# E_Arduino_MEGA2560_ref.net
KiCad netlist of a schematic drawn in EAGLE
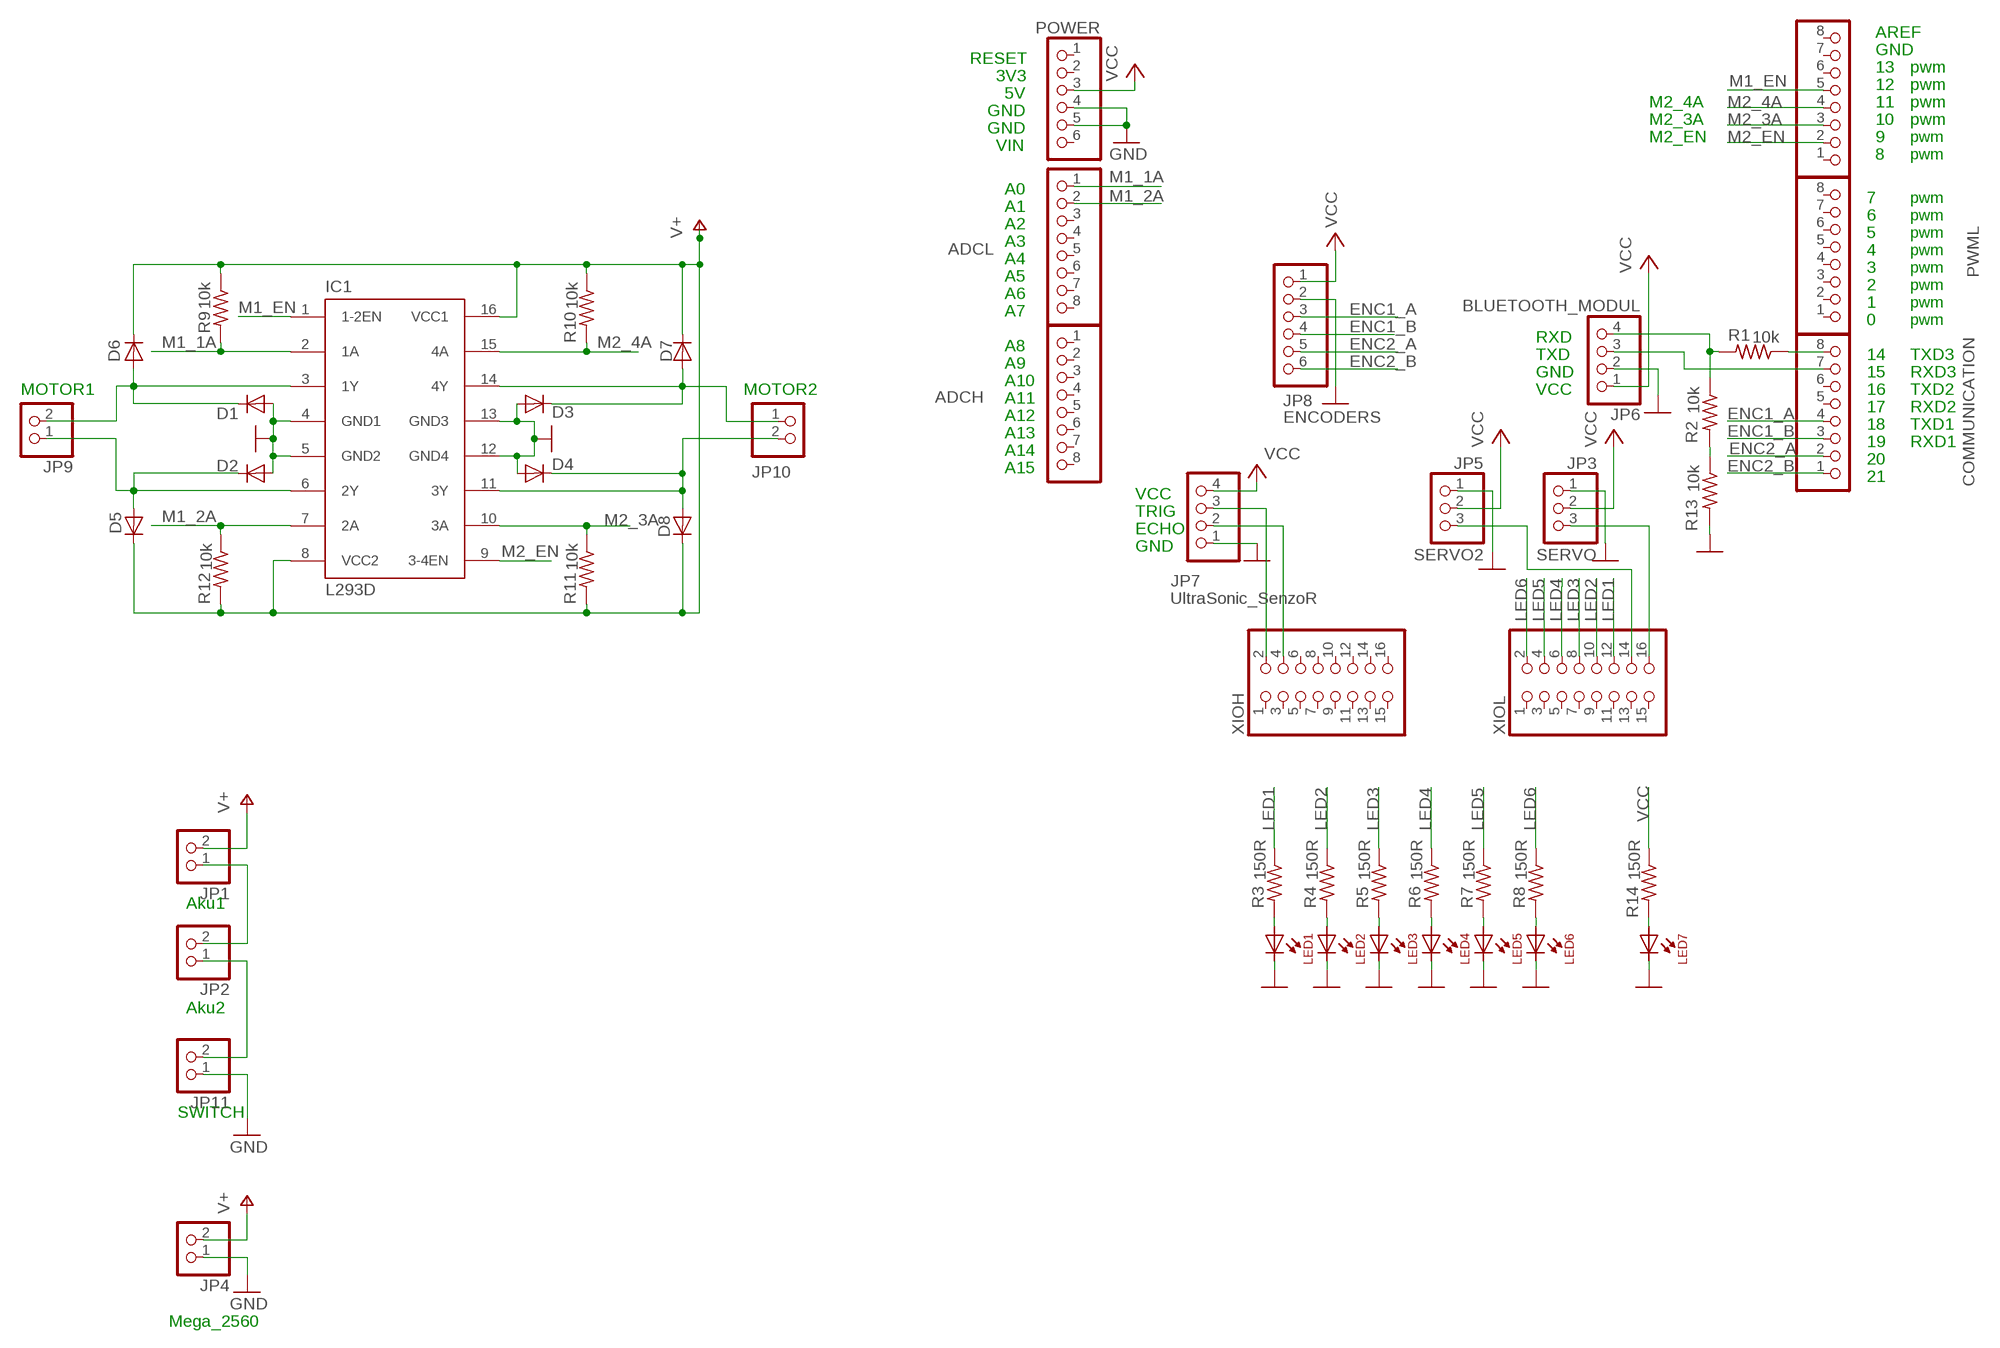
[diagram p0: schematic, sheet 1]

(export (version "E")
  (design (tool "Eeschema 10.0.6"))
  (components
    (comp (ref "ADCH")
      (value "PINHD-1X8")
      (footprint "eagle-import:1X08")
      (libsource (lib "eagle-import") (part "PINHD-1X8"))
    )
    (comp (ref "ADCL")
      (value "PINHD-1X8")
      (footprint "eagle-import:1X08")
      (libsource (lib "eagle-import") (part "PINHD-1X8"))
    )
    (comp (ref "COMMUNICATION")
      (value "PINHD-1X8")
      (footprint "eagle-import:1X08")
      (libsource (lib "eagle-import") (part "PINHD-1X8"))
    )
    (comp (ref "D1")
      (value "PMLL4150")
      (footprint "eagle-import:SOD80C")
      (libsource (lib "eagle-import") (part "PMLL4150"))
    )
    (comp (ref "D2")
      (value "PMLL4150")
      (footprint "eagle-import:SOD80C")
      (libsource (lib "eagle-import") (part "PMLL4150"))
    )
    (comp (ref "D3")
      (value "PMLL4150")
      (footprint "eagle-import:SOD80C")
      (libsource (lib "eagle-import") (part "PMLL4150"))
    )
    (comp (ref "D4")
      (value "PMLL4150")
      (footprint "eagle-import:SOD80C")
      (libsource (lib "eagle-import") (part "PMLL4150"))
    )
    (comp (ref "D5")
      (value "PMLL4150")
      (footprint "eagle-import:SOD80C")
      (libsource (lib "eagle-import") (part "PMLL4150"))
    )
    (comp (ref "D6")
      (value "PMLL4150")
      (footprint "eagle-import:SOD80C")
      (libsource (lib "eagle-import") (part "PMLL4150"))
    )
    (comp (ref "D7")
      (value "PMLL4150")
      (footprint "eagle-import:SOD80C")
      (libsource (lib "eagle-import") (part "PMLL4150"))
    )
    (comp (ref "D8")
      (value "PMLL4150")
      (footprint "eagle-import:SOD80C")
      (libsource (lib "eagle-import") (part "PMLL4150"))
    )
    (comp (ref "IC1")
      (value "L293D")
      (footprint "eagle-import:DIL16")
      (libsource (lib "eagle-import") (part "L293D"))
    )
    (comp (ref "JP1")
      (value "PINHD-1X2")
      (footprint "eagle-import:1X02")
      (libsource (lib "eagle-import") (part "PINHD-1X2"))
    )
    (comp (ref "JP2")
      (value "PINHD-1X2")
      (footprint "eagle-import:1X02")
      (libsource (lib "eagle-import") (part "PINHD-1X2"))
    )
    (comp (ref "JP3")
      (value "SERVO")
      (footprint "eagle-import:1X03")
      (libsource (lib "eagle-import") (part "PINHD-1X3"))
    )
    (comp (ref "JP4")
      (value "PINHD-1X2")
      (footprint "eagle-import:1X02")
      (libsource (lib "eagle-import") (part "PINHD-1X2"))
    )
    (comp (ref "JP5")
      (value "SERVO2")
      (footprint "eagle-import:1X03")
      (libsource (lib "eagle-import") (part "PINHD-1X3"))
    )
    (comp (ref "JP6")
      (value "BLUETOOTH_MODUL")
      (footprint "eagle-import:1X04")
      (libsource (lib "eagle-import") (part "PINHD-1X4"))
    )
    (comp (ref "JP7")
      (value "UltraSonic_SenzoR")
      (footprint "eagle-import:1X04")
      (libsource (lib "eagle-import") (part "PINHD-1X4"))
    )
    (comp (ref "JP8")
      (value "ENCODERS")
      (footprint "eagle-import:1X06")
      (libsource (lib "eagle-import") (part "PINHD-1X6"))
    )
    (comp (ref "JP9")
      (value "PINHD-1X2")
      (footprint "eagle-import:1X02")
      (libsource (lib "eagle-import") (part "PINHD-1X2"))
    )
    (comp (ref "JP10")
      (value "PINHD-1X2")
      (footprint "eagle-import:1X02")
      (libsource (lib "eagle-import") (part "PINHD-1X2"))
    )
    (comp (ref "JP11")
      (value "PINHD-1X2")
      (footprint "eagle-import:1X02")
      (libsource (lib "eagle-import") (part "PINHD-1X2"))
    )
    (comp (ref "LED1")
      (value "LED_Y_SMD")
      (footprint "eagle-import:LED_Y_SMD")
      (libsource (lib "eagle-import") (part "LED_Y_SMD"))
    )
    (comp (ref "LED2")
      (value "LED_Y_SMD")
      (footprint "eagle-import:LED_Y_SMD")
      (libsource (lib "eagle-import") (part "LED_Y_SMD"))
    )
    (comp (ref "LED3")
      (value "LED_Y_SMD")
      (footprint "eagle-import:LED_Y_SMD")
      (libsource (lib "eagle-import") (part "LED_Y_SMD"))
    )
    (comp (ref "LED4")
      (value "LED_Y_SMD")
      (footprint "eagle-import:LED_Y_SMD")
      (libsource (lib "eagle-import") (part "LED_Y_SMD"))
    )
    (comp (ref "LED5")
      (value "LED_Y_SMD")
      (footprint "eagle-import:LED_Y_SMD")
      (libsource (lib "eagle-import") (part "LED_Y_SMD"))
    )
    (comp (ref "LED6")
      (value "LED_Y_SMD")
      (footprint "eagle-import:LED_Y_SMD")
      (libsource (lib "eagle-import") (part "LED_Y_SMD"))
    )
    (comp (ref "LED7")
      (value "LED_Y_SMD")
      (footprint "eagle-import:LED_Y_SMD")
      (libsource (lib "eagle-import") (part "LED_Y_SMD"))
    )
    (comp (ref "POWER")
      (value "PINHD-1X6")
      (footprint "eagle-import:1X06")
      (libsource (lib "eagle-import") (part "PINHD-1X6"))
    )
    (comp (ref "PWMH")
      (value "PINHD-1X8")
      (footprint "eagle-import:1X08")
      (libsource (lib "eagle-import") (part "PINHD-1X8"))
    )
    (comp (ref "PWML")
      (value "PINHD-1X8")
      (footprint "eagle-import:1X08")
      (libsource (lib "eagle-import") (part "PINHD-1X8"))
    )
    (comp (ref "R1")
      (value "10k")
      (footprint "eagle-import:R0805")
      (libsource (lib "eagle-import") (part "R-US_R0805"))
    )
    (comp (ref "R2")
      (value "10k")
      (footprint "eagle-import:R0805")
      (libsource (lib "eagle-import") (part "R-US_R0805"))
    )
    (comp (ref "R3")
      (value "150R")
      (footprint "eagle-import:R0805")
      (libsource (lib "eagle-import") (part "R-US_R0805"))
    )
    (comp (ref "R4")
      (value "150R")
      (footprint "eagle-import:R0805")
      (libsource (lib "eagle-import") (part "R-US_R0805"))
    )
    (comp (ref "R5")
      (value "150R")
      (footprint "eagle-import:R0805")
      (libsource (lib "eagle-import") (part "R-US_R0805"))
    )
    (comp (ref "R6")
      (value "150R")
      (footprint "eagle-import:R0805")
      (libsource (lib "eagle-import") (part "R-US_R0805"))
    )
    (comp (ref "R7")
      (value "150R")
      (footprint "eagle-import:R0805")
      (libsource (lib "eagle-import") (part "R-US_R0805"))
    )
    (comp (ref "R8")
      (value "150R")
      (footprint "eagle-import:R0805")
      (libsource (lib "eagle-import") (part "R-US_R0805"))
    )
    (comp (ref "R9")
      (value "10k")
      (footprint "eagle-import:R0805")
      (libsource (lib "eagle-import") (part "R-US_R0805"))
    )
    (comp (ref "R10")
      (value "10k")
      (footprint "eagle-import:R0805")
      (libsource (lib "eagle-import") (part "R-US_R0805"))
    )
    (comp (ref "R11")
      (value "10k")
      (footprint "eagle-import:R0805")
      (libsource (lib "eagle-import") (part "R-US_R0805"))
    )
    (comp (ref "R12")
      (value "10k")
      (footprint "eagle-import:R0805")
      (libsource (lib "eagle-import") (part "R-US_R0805"))
    )
    (comp (ref "R13")
      (value "10k")
      (footprint "eagle-import:R0805")
      (libsource (lib "eagle-import") (part "R-US_R0805"))
    )
    (comp (ref "R14")
      (value "150R")
      (footprint "eagle-import:R0805")
      (libsource (lib "eagle-import") (part "R-US_R0805"))
    )
    (comp (ref "XIOH")
      (value "PINHD-2X8")
      (footprint "eagle-import:2X08")
      (libsource (lib "eagle-import") (part "PINHD-2X8"))
    )
    (comp (ref "XIOL")
      (value "PINHD-2X8")
      (footprint "eagle-import:2X08")
      (libsource (lib "eagle-import") (part "PINHD-2X8"))
    )
  )
  (nets
    (net (code "1") (name "/ENC1_A") (class "Default")
      (node (ref "COMMUNICATION") (pin "4") (pinfunction "4_4") (pintype "passive"))
      (node (ref "JP8") (pin "3") (pinfunction "3_3") (pintype "passive"))
    )
    (net (code "2") (name "/ENC1_B") (class "Default")
      (node (ref "COMMUNICATION") (pin "3") (pinfunction "3_3") (pintype "passive"))
      (node (ref "JP8") (pin "4") (pinfunction "4_4") (pintype "passive"))
    )
    (net (code "3") (name "/ENC2_A") (class "Default")
      (node (ref "COMMUNICATION") (pin "2") (pinfunction "2_2") (pintype "passive"))
      (node (ref "JP8") (pin "5") (pinfunction "5_5") (pintype "passive"))
    )
    (net (code "4") (name "/ENC2_B") (class "Default")
      (node (ref "COMMUNICATION") (pin "1") (pinfunction "1_1") (pintype "passive"))
      (node (ref "JP8") (pin "6") (pinfunction "6_6") (pintype "passive"))
    )
    (net (code "5") (name "/LED1") (class "Default")
      (node (ref "R3") (pin "1") (pinfunction "1_1") (pintype "passive"))
      (node (ref "XIOL") (pin "12") (pinfunction "12_12") (pintype "passive"))
    )
    (net (code "6") (name "/LED2") (class "Default")
      (node (ref "R4") (pin "1") (pinfunction "1_1") (pintype "passive"))
      (node (ref "XIOL") (pin "10") (pinfunction "10_10") (pintype "passive"))
    )
    (net (code "7") (name "/LED3") (class "Default")
      (node (ref "R5") (pin "1") (pinfunction "1_1") (pintype "passive"))
      (node (ref "XIOL") (pin "8") (pinfunction "8_8") (pintype "passive"))
    )
    (net (code "8") (name "/LED4") (class "Default")
      (node (ref "R6") (pin "1") (pinfunction "1_1") (pintype "passive"))
      (node (ref "XIOL") (pin "6") (pinfunction "6_6") (pintype "passive"))
    )
    (net (code "9") (name "/LED5") (class "Default")
      (node (ref "R7") (pin "1") (pinfunction "1_1") (pintype "passive"))
      (node (ref "XIOL") (pin "4") (pinfunction "4_4") (pintype "passive"))
    )
    (net (code "10") (name "/LED6") (class "Default")
      (node (ref "R8") (pin "1") (pinfunction "1_1") (pintype "passive"))
      (node (ref "XIOL") (pin "2") (pinfunction "2_2") (pintype "passive"))
    )
    (net (code "11") (name "/M1_1A") (class "Default")
      (node (ref "ADCL") (pin "1") (pinfunction "1_1") (pintype "passive"))
      (node (ref "IC1") (pin "2") (pinfunction "1A_2") (pintype "input"))
      (node (ref "R9") (pin "2") (pinfunction "2_2") (pintype "passive"))
    )
    (net (code "12") (name "/M1_2A") (class "Default")
      (node (ref "ADCL") (pin "2") (pinfunction "2_2") (pintype "passive"))
      (node (ref "IC1") (pin "7") (pinfunction "2A_7") (pintype "input"))
      (node (ref "R12") (pin "1") (pinfunction "1_1") (pintype "passive"))
    )
    (net (code "13") (name "/M1_EN") (class "Default")
      (node (ref "IC1") (pin "1") (pinfunction "1-2EN_1") (pintype "input"))
      (node (ref "PWMH") (pin "5") (pinfunction "5_5") (pintype "passive"))
    )
    (net (code "14") (name "/M2_3A") (class "Default")
      (node (ref "IC1") (pin "10") (pinfunction "3A_10") (pintype "input"))
      (node (ref "PWMH") (pin "3") (pinfunction "3_3") (pintype "passive"))
      (node (ref "R11") (pin "1") (pinfunction "1_1") (pintype "passive"))
    )
    (net (code "15") (name "/M2_4A") (class "Default")
      (node (ref "IC1") (pin "15") (pinfunction "4A_15") (pintype "input"))
      (node (ref "PWMH") (pin "4") (pinfunction "4_4") (pintype "passive"))
      (node (ref "R10") (pin "2") (pinfunction "2_2") (pintype "passive"))
    )
    (net (code "16") (name "/M2_EN") (class "Default")
      (node (ref "IC1") (pin "9") (pinfunction "3-4EN_9") (pintype "input"))
      (node (ref "PWMH") (pin "2") (pinfunction "2_2") (pintype "passive"))
    )
    (net (code "17") (name "GND") (class "Default")
      (node (ref "D1") (pin "A") (pinfunction "A_A") (pintype "passive"))
      (node (ref "D2") (pin "A") (pinfunction "A_A") (pintype "passive"))
      (node (ref "D3") (pin "A") (pinfunction "A_A") (pintype "passive"))
      (node (ref "D4") (pin "A") (pinfunction "A_A") (pintype "passive"))
      (node (ref "IC1") (pin "12") (pinfunction "GND4_12") (pintype "power_in"))
      (node (ref "IC1") (pin "13") (pinfunction "GND3_13") (pintype "power_in"))
      (node (ref "IC1") (pin "4") (pinfunction "GND1_4") (pintype "power_in"))
      (node (ref "IC1") (pin "5") (pinfunction "GND2_5") (pintype "power_in"))
      (node (ref "JP11") (pin "1") (pinfunction "1_1") (pintype "passive"))
      (node (ref "JP3") (pin "1") (pinfunction "1_1") (pintype "passive"))
      (node (ref "JP4") (pin "1") (pinfunction "1_1") (pintype "passive"))
      (node (ref "JP5") (pin "1") (pinfunction "1_1") (pintype "passive"))
      (node (ref "JP6") (pin "2") (pinfunction "2_2") (pintype "passive"))
      (node (ref "JP7") (pin "1") (pinfunction "1_1") (pintype "passive"))
      (node (ref "JP8") (pin "2") (pinfunction "2_2") (pintype "passive"))
      (node (ref "LED1") (pin "CATHODE") (pinfunction "CATHODE_CATHODE") (pintype "bidirectional"))
      (node (ref "LED2") (pin "CATHODE") (pinfunction "CATHODE_CATHODE") (pintype "bidirectional"))
      (node (ref "LED3") (pin "CATHODE") (pinfunction "CATHODE_CATHODE") (pintype "bidirectional"))
      (node (ref "LED4") (pin "CATHODE") (pinfunction "CATHODE_CATHODE") (pintype "bidirectional"))
      (node (ref "LED5") (pin "CATHODE") (pinfunction "CATHODE_CATHODE") (pintype "bidirectional"))
      (node (ref "LED6") (pin "CATHODE") (pinfunction "CATHODE_CATHODE") (pintype "bidirectional"))
      (node (ref "LED7") (pin "CATHODE") (pinfunction "CATHODE_CATHODE") (pintype "bidirectional"))
      (node (ref "POWER") (pin "4") (pinfunction "4_4") (pintype "passive"))
      (node (ref "POWER") (pin "5") (pinfunction "5_5") (pintype "passive"))
      (node (ref "R13") (pin "2") (pinfunction "2_2") (pintype "passive"))
    )
    (net (code "18") (name "Net-(COMMUNICATION-Pad7)") (class "Default")
      (node (ref "COMMUNICATION") (pin "7") (pinfunction "7_7") (pintype "passive"))
      (node (ref "JP6") (pin "3") (pinfunction "3_3") (pintype "passive"))
    )
    (net (code "19") (name "Net-(COMMUNICATION-Pad8)") (class "Default")
      (node (ref "COMMUNICATION") (pin "8") (pinfunction "8_8") (pintype "passive"))
      (node (ref "R1") (pin "1") (pinfunction "1_1") (pintype "passive"))
    )
    (net (code "20") (name "Net-(IC1-1Y)") (class "Default")
      (node (ref "D1") (pin "C") (pinfunction "C_C") (pintype "passive"))
      (node (ref "D6") (pin "A") (pinfunction "A_A") (pintype "passive"))
      (node (ref "IC1") (pin "3") (pinfunction "1Y_3") (pintype "output"))
      (node (ref "JP9") (pin "2") (pinfunction "2_2") (pintype "passive"))
    )
    (net (code "21") (name "Net-(IC1-2Y)") (class "Default")
      (node (ref "D2") (pin "C") (pinfunction "C_C") (pintype "passive"))
      (node (ref "D5") (pin "A") (pinfunction "A_A") (pintype "passive"))
      (node (ref "IC1") (pin "6") (pinfunction "2Y_6") (pintype "output"))
      (node (ref "JP9") (pin "1") (pinfunction "1_1") (pintype "passive"))
    )
    (net (code "22") (name "Net-(IC1-3Y)") (class "Default")
      (node (ref "D4") (pin "C") (pinfunction "C_C") (pintype "passive"))
      (node (ref "D8") (pin "A") (pinfunction "A_A") (pintype "passive"))
      (node (ref "IC1") (pin "11") (pinfunction "3Y_11") (pintype "output"))
      (node (ref "JP10") (pin "2") (pinfunction "2_2") (pintype "passive"))
    )
    (net (code "23") (name "Net-(IC1-4Y)") (class "Default")
      (node (ref "D3") (pin "C") (pinfunction "C_C") (pintype "passive"))
      (node (ref "D7") (pin "A") (pinfunction "A_A") (pintype "passive"))
      (node (ref "IC1") (pin "14") (pinfunction "4Y_14") (pintype "output"))
      (node (ref "JP10") (pin "1") (pinfunction "1_1") (pintype "passive"))
    )
    (net (code "24") (name "Net-(JP1-Pad1)") (class "Default")
      (node (ref "JP1") (pin "1") (pinfunction "1_1") (pintype "passive"))
      (node (ref "JP2") (pin "2") (pinfunction "2_2") (pintype "passive"))
    )
    (net (code "25") (name "Net-(JP3-Pad3)") (class "Default")
      (node (ref "JP3") (pin "3") (pinfunction "3_3") (pintype "passive"))
      (node (ref "XIOL") (pin "16") (pinfunction "16_16") (pintype "passive"))
    )
    (net (code "26") (name "Net-(JP5-Pad3)") (class "Default")
      (node (ref "JP5") (pin "3") (pinfunction "3_3") (pintype "passive"))
      (node (ref "XIOL") (pin "14") (pinfunction "14_14") (pintype "passive"))
    )
    (net (code "27") (name "Net-(JP6-Pad4)") (class "Default")
      (node (ref "JP6") (pin "4") (pinfunction "4_4") (pintype "passive"))
      (node (ref "R1") (pin "2") (pinfunction "2_2") (pintype "passive"))
      (node (ref "R2") (pin "1") (pinfunction "1_1") (pintype "passive"))
    )
    (net (code "28") (name "Net-(JP7-Pad2)") (class "Default")
      (node (ref "JP7") (pin "2") (pinfunction "2_2") (pintype "passive"))
      (node (ref "XIOH") (pin "4") (pinfunction "4_4") (pintype "passive"))
    )
    (net (code "29") (name "Net-(JP7-Pad3)") (class "Default")
      (node (ref "JP7") (pin "3") (pinfunction "3_3") (pintype "passive"))
      (node (ref "XIOH") (pin "2") (pinfunction "2_2") (pintype "passive"))
    )
    (net (code "30") (name "Net-(JP11-Pad2)") (class "Default")
      (node (ref "JP11") (pin "2") (pinfunction "2_2") (pintype "passive"))
      (node (ref "JP2") (pin "1") (pinfunction "1_1") (pintype "passive"))
    )
    (net (code "31") (name "Net-(LED1-PadANODE)") (class "Default")
      (node (ref "LED1") (pin "ANODE") (pinfunction "ANODE_ANODE") (pintype "bidirectional"))
      (node (ref "R3") (pin "2") (pinfunction "2_2") (pintype "passive"))
    )
    (net (code "32") (name "Net-(LED2-PadANODE)") (class "Default")
      (node (ref "LED2") (pin "ANODE") (pinfunction "ANODE_ANODE") (pintype "bidirectional"))
      (node (ref "R4") (pin "2") (pinfunction "2_2") (pintype "passive"))
    )
    (net (code "33") (name "Net-(LED3-PadANODE)") (class "Default")
      (node (ref "LED3") (pin "ANODE") (pinfunction "ANODE_ANODE") (pintype "bidirectional"))
      (node (ref "R5") (pin "2") (pinfunction "2_2") (pintype "passive"))
    )
    (net (code "34") (name "Net-(LED4-PadANODE)") (class "Default")
      (node (ref "LED4") (pin "ANODE") (pinfunction "ANODE_ANODE") (pintype "bidirectional"))
      (node (ref "R6") (pin "2") (pinfunction "2_2") (pintype "passive"))
    )
    (net (code "35") (name "Net-(LED5-PadANODE)") (class "Default")
      (node (ref "LED5") (pin "ANODE") (pinfunction "ANODE_ANODE") (pintype "bidirectional"))
      (node (ref "R7") (pin "2") (pinfunction "2_2") (pintype "passive"))
    )
    (net (code "36") (name "Net-(LED6-PadANODE)") (class "Default")
      (node (ref "LED6") (pin "ANODE") (pinfunction "ANODE_ANODE") (pintype "bidirectional"))
      (node (ref "R8") (pin "2") (pinfunction "2_2") (pintype "passive"))
    )
    (net (code "37") (name "Net-(LED7-PadANODE)") (class "Default")
      (node (ref "LED7") (pin "ANODE") (pinfunction "ANODE_ANODE") (pintype "bidirectional"))
      (node (ref "R14") (pin "2") (pinfunction "2_2") (pintype "passive"))
    )
    (net (code "38") (name "Net-(R13-Pad1)") (class "Default")
      (node (ref "R13") (pin "1") (pinfunction "1_1") (pintype "passive"))
      (node (ref "R2") (pin "2") (pinfunction "2_2") (pintype "passive"))
    )
    (net (code "39") (name "V+") (class "Default")
      (node (ref "D5") (pin "C") (pinfunction "C_C") (pintype "passive"))
      (node (ref "D6") (pin "C") (pinfunction "C_C") (pintype "passive"))
      (node (ref "D7") (pin "C") (pinfunction "C_C") (pintype "passive"))
      (node (ref "D8") (pin "C") (pinfunction "C_C") (pintype "passive"))
      (node (ref "IC1") (pin "16") (pinfunction "VCC1_16") (pintype "power_in"))
      (node (ref "IC1") (pin "8") (pinfunction "VCC2_8") (pintype "power_in"))
      (node (ref "JP1") (pin "2") (pinfunction "2_2") (pintype "passive"))
      (node (ref "JP4") (pin "2") (pinfunction "2_2") (pintype "passive"))
      (node (ref "R10") (pin "1") (pinfunction "1_1") (pintype "passive"))
      (node (ref "R11") (pin "2") (pinfunction "2_2") (pintype "passive"))
      (node (ref "R12") (pin "2") (pinfunction "2_2") (pintype "passive"))
      (node (ref "R9") (pin "1") (pinfunction "1_1") (pintype "passive"))
    )
    (net (code "40") (name "VCC") (class "Default")
      (node (ref "JP3") (pin "2") (pinfunction "2_2") (pintype "passive"))
      (node (ref "JP5") (pin "2") (pinfunction "2_2") (pintype "passive"))
      (node (ref "JP6") (pin "1") (pinfunction "1_1") (pintype "passive"))
      (node (ref "JP7") (pin "4") (pinfunction "4_4") (pintype "passive"))
      (node (ref "JP8") (pin "1") (pinfunction "1_1") (pintype "passive"))
      (node (ref "POWER") (pin "3") (pinfunction "3_3") (pintype "passive"))
      (node (ref "R14") (pin "1") (pinfunction "1_1") (pintype "passive"))
    )
    (net (code "41") (name "unconnected-(ADCH-Pad1)") (class "Default")
      (node (ref "ADCH") (pin "1") (pinfunction "1_1") (pintype "passive"))
    )
    (net (code "42") (name "unconnected-(ADCH-Pad2)") (class "Default")
      (node (ref "ADCH") (pin "2") (pinfunction "2_2") (pintype "passive"))
    )
    (net (code "43") (name "unconnected-(ADCH-Pad3)") (class "Default")
      (node (ref "ADCH") (pin "3") (pinfunction "3_3") (pintype "passive"))
    )
    (net (code "44") (name "unconnected-(ADCH-Pad4)") (class "Default")
      (node (ref "ADCH") (pin "4") (pinfunction "4_4") (pintype "passive"))
    )
    (net (code "45") (name "unconnected-(ADCH-Pad5)") (class "Default")
      (node (ref "ADCH") (pin "5") (pinfunction "5_5") (pintype "passive"))
    )
    (net (code "46") (name "unconnected-(ADCH-Pad6)") (class "Default")
      (node (ref "ADCH") (pin "6") (pinfunction "6_6") (pintype "passive"))
    )
    (net (code "47") (name "unconnected-(ADCH-Pad7)") (class "Default")
      (node (ref "ADCH") (pin "7") (pinfunction "7_7") (pintype "passive"))
    )
    (net (code "48") (name "unconnected-(ADCH-Pad8)") (class "Default")
      (node (ref "ADCH") (pin "8") (pinfunction "8_8") (pintype "passive"))
    )
    (net (code "49") (name "unconnected-(ADCL-Pad3)") (class "Default")
      (node (ref "ADCL") (pin "3") (pinfunction "3_3") (pintype "passive"))
    )
    (net (code "50") (name "unconnected-(ADCL-Pad4)") (class "Default")
      (node (ref "ADCL") (pin "4") (pinfunction "4_4") (pintype "passive"))
    )
    (net (code "51") (name "unconnected-(ADCL-Pad5)") (class "Default")
      (node (ref "ADCL") (pin "5") (pinfunction "5_5") (pintype "passive"))
    )
    (net (code "52") (name "unconnected-(ADCL-Pad6)") (class "Default")
      (node (ref "ADCL") (pin "6") (pinfunction "6_6") (pintype "passive"))
    )
    (net (code "53") (name "unconnected-(ADCL-Pad7)") (class "Default")
      (node (ref "ADCL") (pin "7") (pinfunction "7_7") (pintype "passive"))
    )
    (net (code "54") (name "unconnected-(ADCL-Pad8)") (class "Default")
      (node (ref "ADCL") (pin "8") (pinfunction "8_8") (pintype "passive"))
    )
    (net (code "55") (name "unconnected-(COMMUNICATION-Pad5)") (class "Default")
      (node (ref "COMMUNICATION") (pin "5") (pinfunction "5_5") (pintype "passive"))
    )
    (net (code "56") (name "unconnected-(COMMUNICATION-Pad6)") (class "Default")
      (node (ref "COMMUNICATION") (pin "6") (pinfunction "6_6") (pintype "passive"))
    )
    (net (code "57") (name "unconnected-(POWER-Pad1)") (class "Default")
      (node (ref "POWER") (pin "1") (pinfunction "1_1") (pintype "passive"))
    )
    (net (code "58") (name "unconnected-(POWER-Pad2)") (class "Default")
      (node (ref "POWER") (pin "2") (pinfunction "2_2") (pintype "passive"))
    )
    (net (code "59") (name "unconnected-(POWER-Pad6)") (class "Default")
      (node (ref "POWER") (pin "6") (pinfunction "6_6") (pintype "passive"))
    )
    (net (code "60") (name "unconnected-(PWMH-Pad1)") (class "Default")
      (node (ref "PWMH") (pin "1") (pinfunction "1_1") (pintype "passive"))
    )
    (net (code "61") (name "unconnected-(PWMH-Pad6)") (class "Default")
      (node (ref "PWMH") (pin "6") (pinfunction "6_6") (pintype "passive"))
    )
    (net (code "62") (name "unconnected-(PWMH-Pad7)") (class "Default")
      (node (ref "PWMH") (pin "7") (pinfunction "7_7") (pintype "passive"))
    )
    (net (code "63") (name "unconnected-(PWMH-Pad8)") (class "Default")
      (node (ref "PWMH") (pin "8") (pinfunction "8_8") (pintype "passive"))
    )
    (net (code "64") (name "unconnected-(PWML-Pad1)") (class "Default")
      (node (ref "PWML") (pin "1") (pinfunction "1_1") (pintype "passive"))
    )
    (net (code "65") (name "unconnected-(PWML-Pad2)") (class "Default")
      (node (ref "PWML") (pin "2") (pinfunction "2_2") (pintype "passive"))
    )
    (net (code "66") (name "unconnected-(PWML-Pad3)") (class "Default")
      (node (ref "PWML") (pin "3") (pinfunction "3_3") (pintype "passive"))
    )
    (net (code "67") (name "unconnected-(PWML-Pad4)") (class "Default")
      (node (ref "PWML") (pin "4") (pinfunction "4_4") (pintype "passive"))
    )
    (net (code "68") (name "unconnected-(PWML-Pad5)") (class "Default")
      (node (ref "PWML") (pin "5") (pinfunction "5_5") (pintype "passive"))
    )
    (net (code "69") (name "unconnected-(PWML-Pad6)") (class "Default")
      (node (ref "PWML") (pin "6") (pinfunction "6_6") (pintype "passive"))
    )
    (net (code "70") (name "unconnected-(PWML-Pad7)") (class "Default")
      (node (ref "PWML") (pin "7") (pinfunction "7_7") (pintype "passive"))
    )
    (net (code "71") (name "unconnected-(PWML-Pad8)") (class "Default")
      (node (ref "PWML") (pin "8") (pinfunction "8_8") (pintype "passive"))
    )
    (net (code "72") (name "unconnected-(XIOH-Pad1)") (class "Default")
      (node (ref "XIOH") (pin "1") (pinfunction "1_1") (pintype "passive"))
    )
    (net (code "73") (name "unconnected-(XIOH-Pad3)") (class "Default")
      (node (ref "XIOH") (pin "3") (pinfunction "3_3") (pintype "passive"))
    )
    (net (code "74") (name "unconnected-(XIOH-Pad5)") (class "Default")
      (node (ref "XIOH") (pin "5") (pinfunction "5_5") (pintype "passive"))
    )
    (net (code "75") (name "unconnected-(XIOH-Pad6)") (class "Default")
      (node (ref "XIOH") (pin "6") (pinfunction "6_6") (pintype "passive"))
    )
    (net (code "76") (name "unconnected-(XIOH-Pad7)") (class "Default")
      (node (ref "XIOH") (pin "7") (pinfunction "7_7") (pintype "passive"))
    )
    (net (code "77") (name "unconnected-(XIOH-Pad8)") (class "Default")
      (node (ref "XIOH") (pin "8") (pinfunction "8_8") (pintype "passive"))
    )
    (net (code "78") (name "unconnected-(XIOH-Pad9)") (class "Default")
      (node (ref "XIOH") (pin "9") (pinfunction "9_9") (pintype "passive"))
    )
    (net (code "79") (name "unconnected-(XIOH-Pad10)") (class "Default")
      (node (ref "XIOH") (pin "10") (pinfunction "10_10") (pintype "passive"))
    )
    (net (code "80") (name "unconnected-(XIOH-Pad11)") (class "Default")
      (node (ref "XIOH") (pin "11") (pinfunction "11_11") (pintype "passive"))
    )
    (net (code "81") (name "unconnected-(XIOH-Pad12)") (class "Default")
      (node (ref "XIOH") (pin "12") (pinfunction "12_12") (pintype "passive"))
    )
    (net (code "82") (name "unconnected-(XIOH-Pad13)") (class "Default")
      (node (ref "XIOH") (pin "13") (pinfunction "13_13") (pintype "passive"))
    )
    (net (code "83") (name "unconnected-(XIOH-Pad14)") (class "Default")
      (node (ref "XIOH") (pin "14") (pinfunction "14_14") (pintype "passive"))
    )
    (net (code "84") (name "unconnected-(XIOH-Pad15)") (class "Default")
      (node (ref "XIOH") (pin "15") (pinfunction "15_15") (pintype "passive"))
    )
    (net (code "85") (name "unconnected-(XIOH-Pad16)") (class "Default")
      (node (ref "XIOH") (pin "16") (pinfunction "16_16") (pintype "passive"))
    )
    (net (code "86") (name "unconnected-(XIOL-Pad1)") (class "Default")
      (node (ref "XIOL") (pin "1") (pinfunction "1_1") (pintype "passive"))
    )
    (net (code "87") (name "unconnected-(XIOL-Pad3)") (class "Default")
      (node (ref "XIOL") (pin "3") (pinfunction "3_3") (pintype "passive"))
    )
    (net (code "88") (name "unconnected-(XIOL-Pad5)") (class "Default")
      (node (ref "XIOL") (pin "5") (pinfunction "5_5") (pintype "passive"))
    )
    (net (code "89") (name "unconnected-(XIOL-Pad7)") (class "Default")
      (node (ref "XIOL") (pin "7") (pinfunction "7_7") (pintype "passive"))
    )
    (net (code "90") (name "unconnected-(XIOL-Pad9)") (class "Default")
      (node (ref "XIOL") (pin "9") (pinfunction "9_9") (pintype "passive"))
    )
    (net (code "91") (name "unconnected-(XIOL-Pad11)") (class "Default")
      (node (ref "XIOL") (pin "11") (pinfunction "11_11") (pintype "passive"))
    )
    (net (code "92") (name "unconnected-(XIOL-Pad13)") (class "Default")
      (node (ref "XIOL") (pin "13") (pinfunction "13_13") (pintype "passive"))
    )
    (net (code "93") (name "unconnected-(XIOL-Pad15)") (class "Default")
      (node (ref "XIOL") (pin "15") (pinfunction "15_15") (pintype "passive"))
    )
  )
)
